# spi_flasher.net
KiCad netlist of a schematic drawn in EAGLE
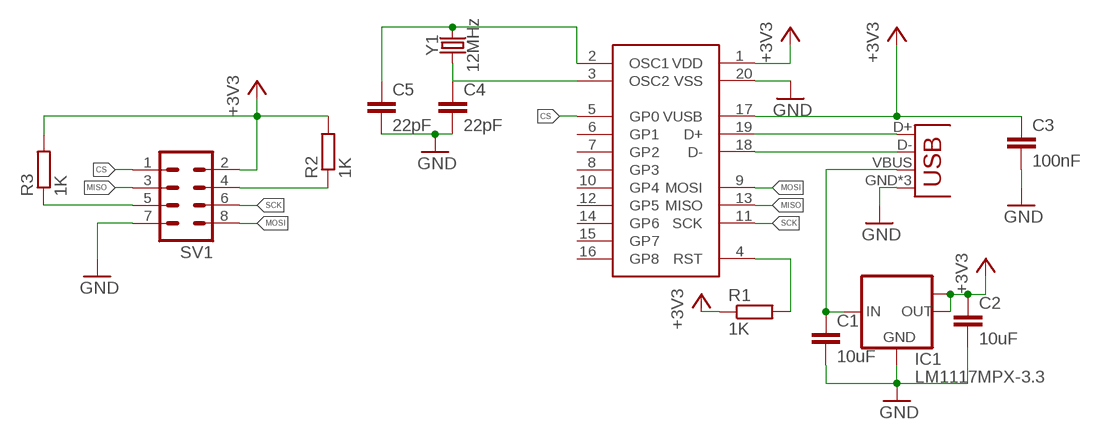
[diagram p0: schematic, sheet 1]

(export (version "E")
  (design (tool "Eeschema 10.0.6"))
  (components
    (comp (ref "C1")
      (value "10uF")
      (footprint "eagle-import:C1206")
      (libsource (lib "eagle-import") (part "C-EUC1206"))
    )
    (comp (ref "C2")
      (value "10uF")
      (footprint "eagle-import:C1206")
      (libsource (lib "eagle-import") (part "C-EUC1206"))
    )
    (comp (ref "C3")
      (value "100nF")
      (footprint "eagle-import:C0603")
      (libsource (lib "eagle-import") (part "C-EUC0603"))
    )
    (comp (ref "C4")
      (value "22pF")
      (footprint "eagle-import:C0603")
      (libsource (lib "eagle-import") (part "C-EUC0603"))
    )
    (comp (ref "C5")
      (value "22pF")
      (footprint "eagle-import:C0603")
      (libsource (lib "eagle-import") (part "C-EUC0603"))
    )
    (comp (ref "IC1")
      (value "LM1117MPX-3.3")
      (footprint "eagle-import:SOT223")
      (libsource (lib "eagle-import") (part "LM1117MPX-3.3"))
    )
    (comp (ref "R1")
      (value "1K")
      (footprint "eagle-import:R0603")
      (libsource (lib "eagle-import") (part "R-EU_R0603"))
    )
    (comp (ref "R2")
      (value "1K")
      (footprint "eagle-import:R0603")
      (libsource (lib "eagle-import") (part "R-EU_R0603"))
    )
    (comp (ref "R3")
      (value "1K")
      (footprint "eagle-import:R0603")
      (libsource (lib "eagle-import") (part "R-EU_R0603"))
    )
    (comp (ref "SV1")
      (value "MA04-2")
      (footprint "eagle-import:MA04-2")
      (libsource (lib "eagle-import") (part "MA04-2"))
    )
    (comp (ref "U$1")
      (value "MCP2210-I/SO")
      (footprint "eagle-import:SO20L")
      (libsource (lib "eagle-import") (part "MCP2210-I/SO"))
    )
    (comp (ref "X1")
      (value "USBPTH")
      (footprint "eagle-import:USB-B-PTH")
      (libsource (lib "eagle-import") (part "USBPTH"))
    )
    (comp (ref "Y1")
      (value "12MHz")
      (footprint "eagle-import:CRYSTAL-SMD-3.2X2.5MM")
      (libsource (lib "eagle-import") (part "CRYSTALSMD-3.2X2.5"))
    )
  )
  (nets
    (net (code "1") (name "+3V3") (class "Default")
      (node (ref "C2") (pin "1") (pinfunction "1_1") (pintype "passive"))
      (node (ref "C3") (pin "1") (pinfunction "1_1") (pintype "passive"))
      (node (ref "IC1") (pin "2") (pinfunction "OUT_2") (pintype "passive"))
      (node (ref "IC1") (pin "TAB") (pinfunction "OUT1_TAB") (pintype "passive"))
      (node (ref "R1") (pin "1") (pinfunction "1_1") (pintype "passive"))
      (node (ref "R2") (pin "2") (pinfunction "2_2") (pintype "passive"))
      (node (ref "R3") (pin "2") (pinfunction "2_2") (pintype "passive"))
      (node (ref "SV1") (pin "2") (pinfunction "2_2") (pintype "passive"))
      (node (ref "U$1") (pin "1") (pinfunction "VDD_1") (pintype "bidirectional"))
      (node (ref "U$1") (pin "17") (pinfunction "VUSB_17") (pintype "bidirectional"))
    )
    (net (code "2") (name "CS") (class "Default")
      (node (ref "SV1") (pin "1") (pinfunction "1_1") (pintype "passive"))
      (node (ref "U$1") (pin "5") (pinfunction "GP0_5") (pintype "bidirectional"))
    )
    (net (code "3") (name "GND") (class "Default")
      (node (ref "C1") (pin "2") (pinfunction "2_2") (pintype "passive"))
      (node (ref "C2") (pin "2") (pinfunction "2_2") (pintype "passive"))
      (node (ref "C3") (pin "2") (pinfunction "2_2") (pintype "passive"))
      (node (ref "C4") (pin "2") (pinfunction "2_2") (pintype "passive"))
      (node (ref "C5") (pin "2") (pinfunction "2_2") (pintype "passive"))
      (node (ref "IC1") (pin "1") (pinfunction "GND_1") (pintype "input"))
      (node (ref "SV1") (pin "7") (pinfunction "7_7") (pintype "passive"))
      (node (ref "U$1") (pin "20") (pinfunction "VSS_20") (pintype "bidirectional"))
      (node (ref "X1") (pin "GND") (pinfunction "GND_GND") (pintype "bidirectional"))
      (node (ref "X1") (pin "P$1") (pinfunction "GND_P$1") (pintype "bidirectional"))
      (node (ref "X1") (pin "P$2") (pinfunction "GND_P$2") (pintype "bidirectional"))
    )
    (net (code "4") (name "MISO") (class "Default")
      (node (ref "SV1") (pin "3") (pinfunction "3_3") (pintype "passive"))
      (node (ref "U$1") (pin "13") (pinfunction "MISO_13") (pintype "bidirectional"))
    )
    (net (code "5") (name "MOSI") (class "Default")
      (node (ref "SV1") (pin "8") (pinfunction "8_8") (pintype "passive"))
      (node (ref "U$1") (pin "9") (pinfunction "MOSI_9") (pintype "bidirectional"))
    )
    (net (code "6") (name "Net-(IC1-IN)") (class "Default")
      (node (ref "C1") (pin "1") (pinfunction "1_1") (pintype "passive"))
      (node (ref "IC1") (pin "3") (pinfunction "IN_3") (pintype "input"))
      (node (ref "X1") (pin "VBUS") (pinfunction "VBUS_VBUS") (pintype "bidirectional"))
    )
    (net (code "7") (name "Net-(R2-Pad1)") (class "Default")
      (node (ref "R2") (pin "1") (pinfunction "1_1") (pintype "passive"))
      (node (ref "SV1") (pin "4") (pinfunction "4_4") (pintype "passive"))
    )
    (net (code "8") (name "Net-(R3-Pad1)") (class "Default")
      (node (ref "R3") (pin "1") (pinfunction "1_1") (pintype "passive"))
      (node (ref "SV1") (pin "5") (pinfunction "5_5") (pintype "passive"))
    )
    (net (code "9") (name "Net-(U$1-D+)") (class "Default")
      (node (ref "U$1") (pin "19") (pinfunction "D+_19") (pintype "bidirectional"))
      (node (ref "X1") (pin "D+") (pinfunction "D+_D+") (pintype "bidirectional"))
    )
    (net (code "10") (name "Net-(U$1-D-)") (class "Default")
      (node (ref "U$1") (pin "18") (pinfunction "D-_18") (pintype "bidirectional"))
      (node (ref "X1") (pin "D-") (pinfunction "D-_D-") (pintype "bidirectional"))
    )
    (net (code "11") (name "Net-(U$1-OSC1)") (class "Default")
      (node (ref "C5") (pin "1") (pinfunction "1_1") (pintype "passive"))
      (node (ref "U$1") (pin "2") (pinfunction "OSC1_2") (pintype "bidirectional"))
      (node (ref "Y1") (pin "3") (pinfunction "2_3") (pintype "passive"))
    )
    (net (code "12") (name "Net-(U$1-OSC2)") (class "Default")
      (node (ref "C4") (pin "1") (pinfunction "1_1") (pintype "passive"))
      (node (ref "U$1") (pin "3") (pinfunction "OSC2_3") (pintype "bidirectional"))
      (node (ref "Y1") (pin "1") (pinfunction "1_1") (pintype "passive"))
    )
    (net (code "13") (name "Net-(U$1-RST)") (class "Default")
      (node (ref "R1") (pin "2") (pinfunction "2_2") (pintype "passive"))
      (node (ref "U$1") (pin "4") (pinfunction "RST_4") (pintype "bidirectional"))
    )
    (net (code "14") (name "SCK") (class "Default")
      (node (ref "SV1") (pin "6") (pinfunction "6_6") (pintype "passive"))
      (node (ref "U$1") (pin "11") (pinfunction "SCK_11") (pintype "bidirectional"))
    )
    (net (code "15") (name "unconnected-(U$1-GP1-Pad6)") (class "Default")
      (node (ref "U$1") (pin "6") (pinfunction "GP1_6") (pintype "bidirectional"))
    )
    (net (code "16") (name "unconnected-(U$1-GP2-Pad7)") (class "Default")
      (node (ref "U$1") (pin "7") (pinfunction "GP2_7") (pintype "bidirectional"))
    )
    (net (code "17") (name "unconnected-(U$1-GP3-Pad8)") (class "Default")
      (node (ref "U$1") (pin "8") (pinfunction "GP3_8") (pintype "bidirectional"))
    )
    (net (code "18") (name "unconnected-(U$1-GP4-Pad10)") (class "Default")
      (node (ref "U$1") (pin "10") (pinfunction "GP4_10") (pintype "bidirectional"))
    )
    (net (code "19") (name "unconnected-(U$1-GP5-Pad12)") (class "Default")
      (node (ref "U$1") (pin "12") (pinfunction "GP5_12") (pintype "bidirectional"))
    )
    (net (code "20") (name "unconnected-(U$1-GP6-Pad14)") (class "Default")
      (node (ref "U$1") (pin "14") (pinfunction "GP6_14") (pintype "bidirectional"))
    )
    (net (code "21") (name "unconnected-(U$1-GP7-Pad15)") (class "Default")
      (node (ref "U$1") (pin "15") (pinfunction "GP7_15") (pintype "bidirectional"))
    )
    (net (code "22") (name "unconnected-(U$1-GP8-Pad16)") (class "Default")
      (node (ref "U$1") (pin "16") (pinfunction "GP8_16") (pintype "bidirectional"))
    )
  )
)
